# design_12.net
KiCad netlist of a schematic drawn in Altium Designer
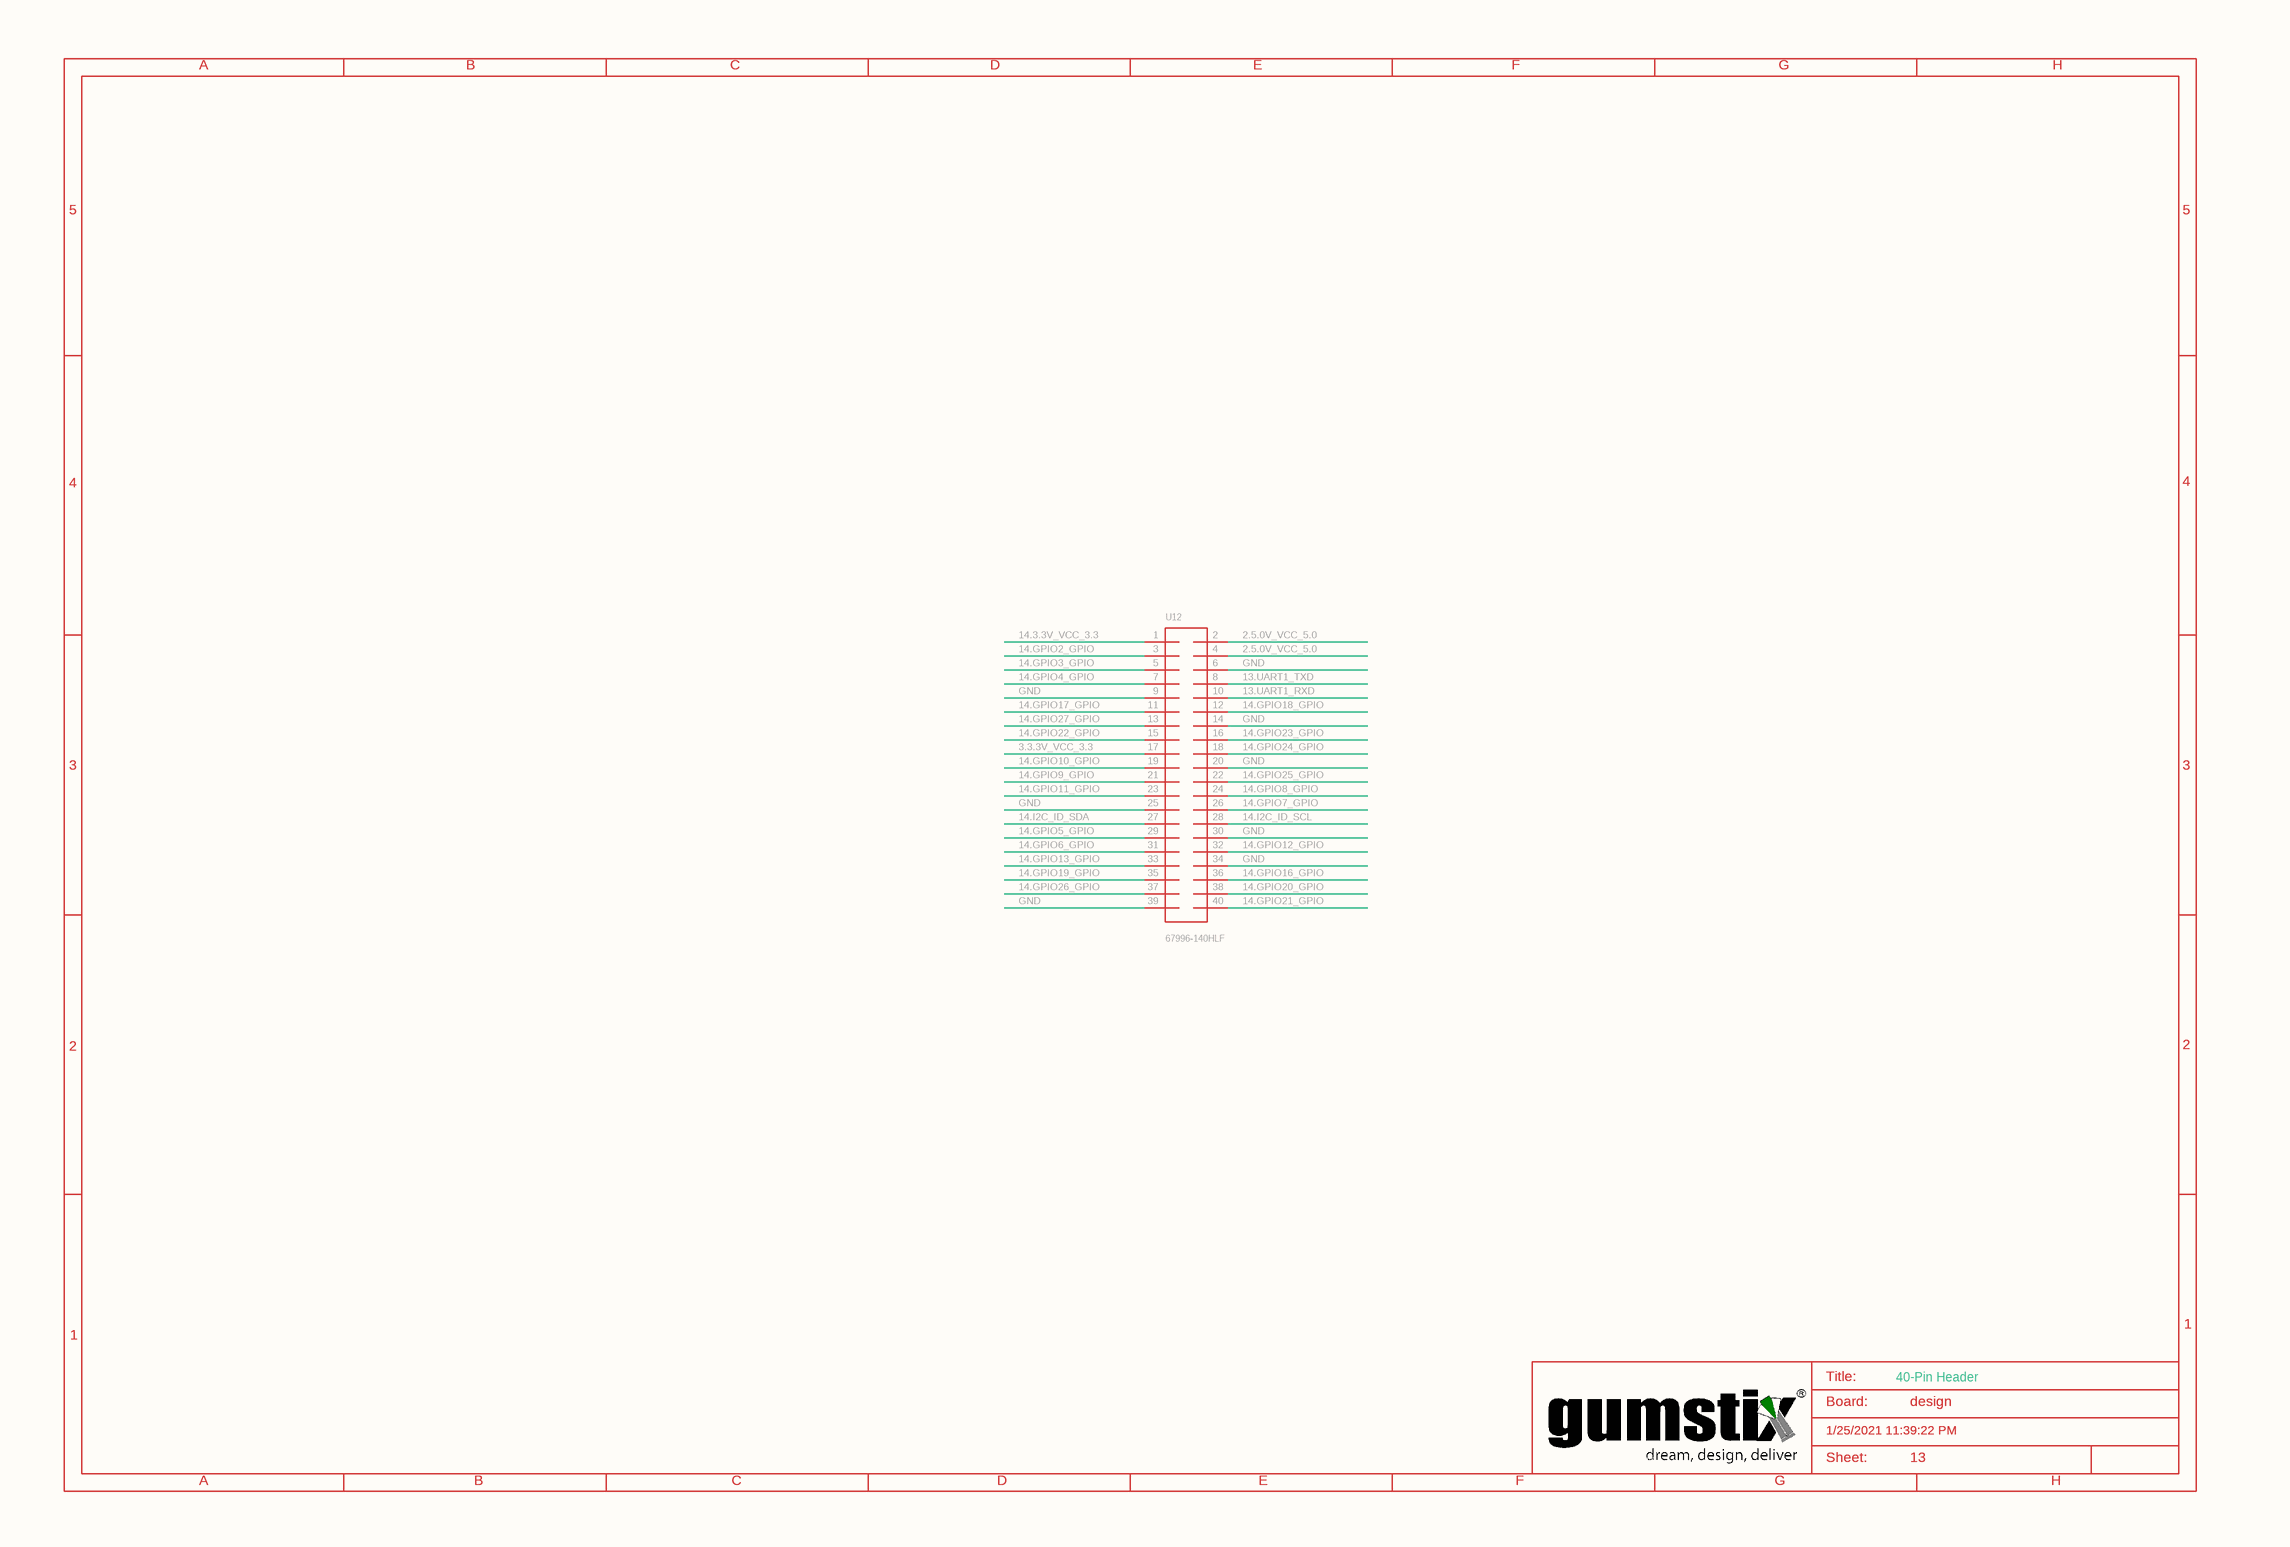
[diagram p0: design_12.SchDoc]

(export (version "E")
  (design (tool "Eeschema 10.0.6"))
  (components
    (comp (ref "U$5")
      (value "A3-L-GUMSTIX")
      (fields
        (field (name "A") "A")
        (field (name "B") "B")
        (field (name "C") "C")
        (field (name "D") "D")
        (field (name "E") "E")
        (field (name "F") "F")
        (field (name "G") "G")
        (field (name "H") "H")
        (field (name "1") "1")
        (field (name "2") "2")
        (field (name "3") "3")
        (field (name "4") "4")
        (field (name "5") "5")
        (field (name "H_1") "H")
        (field (name "G_1") "G")
        (field (name "F_1") "F")
        (field (name "E_1") "E")
        (field (name "D_1") "D")
        (field (name "C_1") "C")
        (field (name "B_1") "B")
        (field (name "A_1") "A")
        (field (name "5_1") "5")
        (field (name "4_1") "4")
        (field (name "3_1") "3")
        (field (name "2_1") "2")
        (field (name "1_1") "1")
        (field (name "DRAWING_NAME") "design")
        (field (name "LAST_DATE_TIME") "1/25/2021 11:39:22 PM")
        (field (name "SHEET") "13")
        (field (name "SHEET_1") "Sheet:")
        (field (name "C:/GUMSTIX/GUMSTIX-LOGO-16.BMP") "C:/Gumstix/gumstix-logo-16.bmp")
        (field (name "TITLE") "Title:")
        (field (name "BOARD") "Board:")
      )
      (libsource (lib "qualified_1") (part "A3-L-GUMSTIX"))
    )
    (comp (ref "U$27")
      (value "A3-L-GUMSTIX")
      (fields
        (field (name "A") "A")
        (field (name "B") "B")
        (field (name "C") "C")
        (field (name "D") "D")
        (field (name "E") "E")
        (field (name "F") "F")
        (field (name "G") "G")
        (field (name "H") "H")
        (field (name "1") "1")
        (field (name "2") "2")
        (field (name "3") "3")
        (field (name "4") "4")
        (field (name "5") "5")
        (field (name "H_1") "H")
        (field (name "G_1") "G")
        (field (name "F_1") "F")
        (field (name "E_1") "E")
        (field (name "D_1") "D")
        (field (name "C_1") "C")
        (field (name "B_1") "B")
        (field (name "A_1") "A")
        (field (name "5_1") "5")
        (field (name "4_1") "4")
        (field (name "3_1") "3")
        (field (name "2_1") "2")
        (field (name "1_1") "1")
        (field (name "DRAWING_NAME") "design")
        (field (name "LAST_DATE_TIME") "1/25/2021 11:39:22 PM")
        (field (name "SHEET") "13")
        (field (name "SHEET_1") "Sheet:")
        (field (name "C:/GUMSTIX/GUMSTIX-LOGO-16.BMP") "C:/Gumstix/gumstix-logo-16.bmp")
        (field (name "TITLE") "Title:")
        (field (name "BOARD") "Board:")
      )
      (libsource (lib "qualified_1") (part "A3-L-GUMSTIX"))
    )
    (comp (ref "U12")
      (value "67996-140HLF")
      (footprint "2X20")
      (libsource (lib "qualified_1") (part "67996-140HLF"))
    )
  )
  (nets
    (net (code "1") (name "/2.5.0V_VCC_5.0") (class "Default")
      (node (ref "U12") (pin "2") (pinfunction "2_2") (pintype "passive"))
      (node (ref "U12") (pin "4") (pinfunction "4_4") (pintype "passive"))
    )
    (net (code "2") (name "/3.3.3V_VCC_3.3") (class "Default")
      (node (ref "U12") (pin "17") (pinfunction "17_17") (pintype "passive"))
    )
    (net (code "3") (name "/13.UART1_RXD") (class "Default")
      (node (ref "U12") (pin "10") (pinfunction "10_10") (pintype "passive"))
    )
    (net (code "4") (name "/13.UART1_TXD") (class "Default")
      (node (ref "U12") (pin "8") (pinfunction "8_8") (pintype "passive"))
    )
    (net (code "5") (name "/14.3.3V_VCC_3.3") (class "Default")
      (node (ref "U12") (pin "1") (pinfunction "1_1") (pintype "passive"))
    )
    (net (code "6") (name "/14.GPIO2_GPIO") (class "Default")
      (node (ref "U12") (pin "3") (pinfunction "3_3") (pintype "passive"))
    )
    (net (code "7") (name "/14.GPIO3_GPIO") (class "Default")
      (node (ref "U12") (pin "5") (pinfunction "5_5") (pintype "passive"))
    )
    (net (code "8") (name "/14.GPIO4_GPIO") (class "Default")
      (node (ref "U12") (pin "7") (pinfunction "7_7") (pintype "passive"))
    )
    (net (code "9") (name "/14.GPIO5_GPIO") (class "Default")
      (node (ref "U12") (pin "29") (pinfunction "29_29") (pintype "passive"))
    )
    (net (code "10") (name "/14.GPIO6_GPIO") (class "Default")
      (node (ref "U12") (pin "31") (pinfunction "31_31") (pintype "passive"))
    )
    (net (code "11") (name "/14.GPIO7_GPIO") (class "Default")
      (node (ref "U12") (pin "26") (pinfunction "26_26") (pintype "passive"))
    )
    (net (code "12") (name "/14.GPIO8_GPIO") (class "Default")
      (node (ref "U12") (pin "24") (pinfunction "24_24") (pintype "passive"))
    )
    (net (code "13") (name "/14.GPIO9_GPIO") (class "Default")
      (node (ref "U12") (pin "21") (pinfunction "21_21") (pintype "passive"))
    )
    (net (code "14") (name "/14.GPIO10_GPIO") (class "Default")
      (node (ref "U12") (pin "19") (pinfunction "19_19") (pintype "passive"))
    )
    (net (code "15") (name "/14.GPIO11_GPIO") (class "Default")
      (node (ref "U12") (pin "23") (pinfunction "23_23") (pintype "passive"))
    )
    (net (code "16") (name "/14.GPIO12_GPIO") (class "Default")
      (node (ref "U12") (pin "32") (pinfunction "32_32") (pintype "passive"))
    )
    (net (code "17") (name "/14.GPIO13_GPIO") (class "Default")
      (node (ref "U12") (pin "33") (pinfunction "33_33") (pintype "passive"))
    )
    (net (code "18") (name "/14.GPIO16_GPIO") (class "Default")
      (node (ref "U12") (pin "36") (pinfunction "36_36") (pintype "passive"))
    )
    (net (code "19") (name "/14.GPIO17_GPIO") (class "Default")
      (node (ref "U12") (pin "11") (pinfunction "11_11") (pintype "passive"))
    )
    (net (code "20") (name "/14.GPIO18_GPIO") (class "Default")
      (node (ref "U12") (pin "12") (pinfunction "12_12") (pintype "passive"))
    )
    (net (code "21") (name "/14.GPIO19_GPIO") (class "Default")
      (node (ref "U12") (pin "35") (pinfunction "35_35") (pintype "passive"))
    )
    (net (code "22") (name "/14.GPIO20_GPIO") (class "Default")
      (node (ref "U12") (pin "38") (pinfunction "38_38") (pintype "passive"))
    )
    (net (code "23") (name "/14.GPIO21_GPIO") (class "Default")
      (node (ref "U12") (pin "40") (pinfunction "40_40") (pintype "passive"))
    )
    (net (code "24") (name "/14.GPIO22_GPIO") (class "Default")
      (node (ref "U12") (pin "15") (pinfunction "15_15") (pintype "passive"))
    )
    (net (code "25") (name "/14.GPIO23_GPIO") (class "Default")
      (node (ref "U12") (pin "16") (pinfunction "16_16") (pintype "passive"))
    )
    (net (code "26") (name "/14.GPIO24_GPIO") (class "Default")
      (node (ref "U12") (pin "18") (pinfunction "18_18") (pintype "passive"))
    )
    (net (code "27") (name "/14.GPIO25_GPIO") (class "Default")
      (node (ref "U12") (pin "22") (pinfunction "22_22") (pintype "passive"))
    )
    (net (code "28") (name "/14.GPIO26_GPIO") (class "Default")
      (node (ref "U12") (pin "37") (pinfunction "37_37") (pintype "passive"))
    )
    (net (code "29") (name "/14.GPIO27_GPIO") (class "Default")
      (node (ref "U12") (pin "13") (pinfunction "13_13") (pintype "passive"))
    )
    (net (code "30") (name "/14.I2C_ID_SCL") (class "Default")
      (node (ref "U12") (pin "28") (pinfunction "28_28") (pintype "passive"))
    )
    (net (code "31") (name "/14.I2C_ID_SDA") (class "Default")
      (node (ref "U12") (pin "27") (pinfunction "27_27") (pintype "passive"))
    )
    (net (code "32") (name "/GND") (class "Default")
      (node (ref "U12") (pin "14") (pinfunction "14_14") (pintype "passive"))
      (node (ref "U12") (pin "20") (pinfunction "20_20") (pintype "passive"))
      (node (ref "U12") (pin "25") (pinfunction "25_25") (pintype "passive"))
      (node (ref "U12") (pin "30") (pinfunction "30_30") (pintype "passive"))
      (node (ref "U12") (pin "34") (pinfunction "34_34") (pintype "passive"))
      (node (ref "U12") (pin "39") (pinfunction "39_39") (pintype "passive"))
      (node (ref "U12") (pin "6") (pinfunction "6_6") (pintype "passive"))
      (node (ref "U12") (pin "9") (pinfunction "9_9") (pintype "passive"))
    )
  )
)
